# Sheet2.net
KiCad netlist of a schematic drawn in Altium Designer
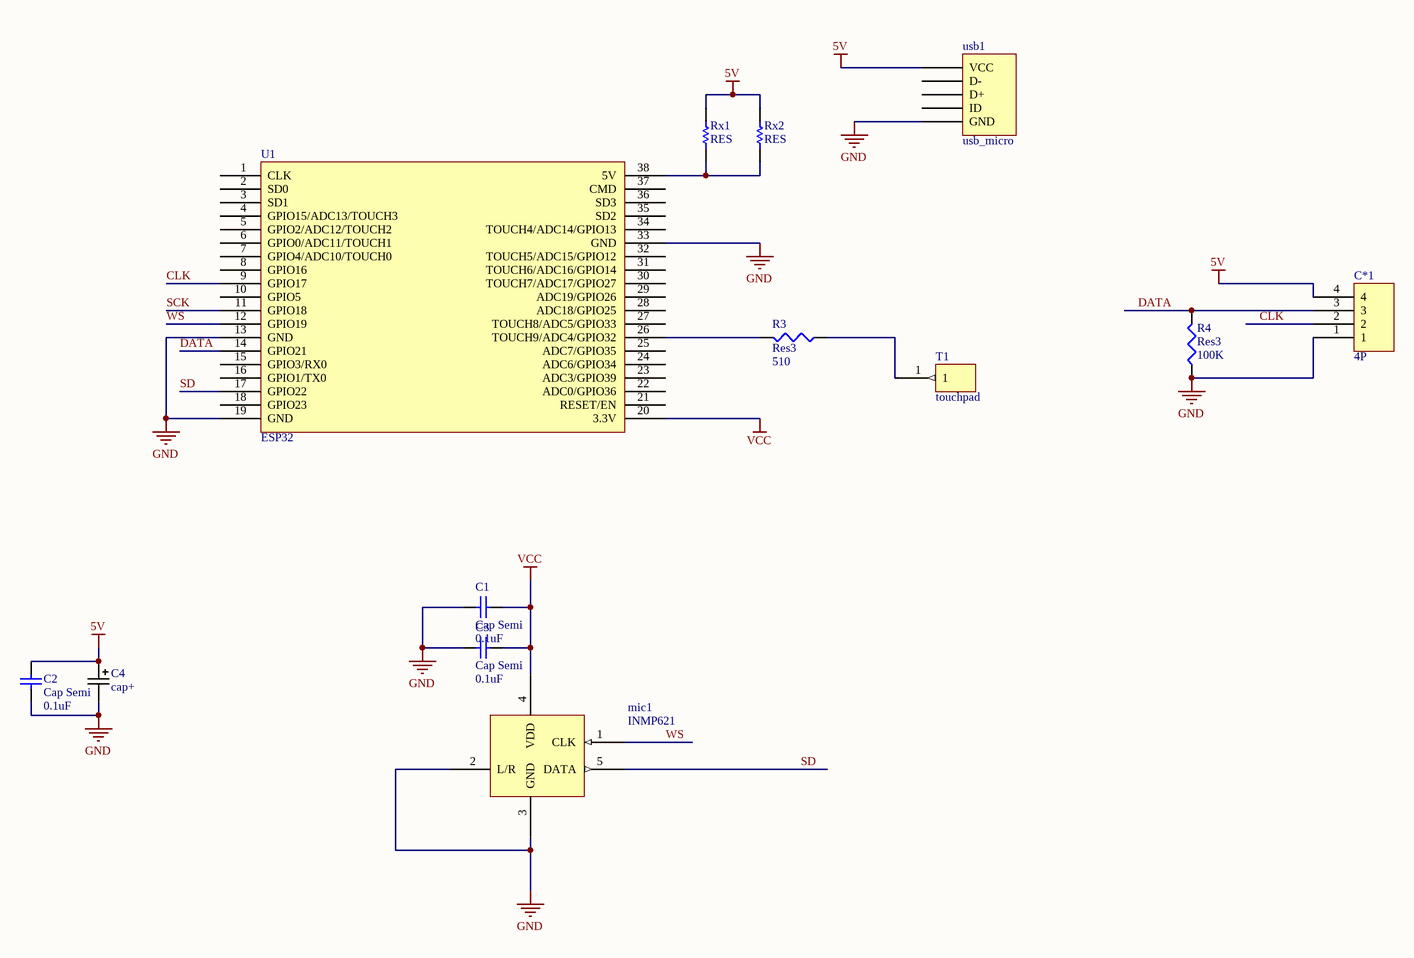
[diagram p0: Sheet2.SchDoc]

(export (version "E")
  (design (tool "Eeschema 10.0.6"))
  (components
    (comp (ref "C*1") (value "4P") (footprint "XH2.54_4P") (libsource (lib "connector") (part "4P")))
    (comp (ref "C1")
      (value "Cap Semi")
      (footprint "1608[0603]")
      (description "Capacitor (Semiconductor SIM Model)")
      (fields (field (name "ALTIUM_VALUE") "0.1uF") (field (name "PUBLISHER") "Altium Limited"))
      (libsource (lib "Miscellaneous Devices") (part "Cap Semi"))
    )
    (comp (ref "C2")
      (value "Cap Semi")
      (footprint "1608[0603]")
      (description "Capacitor (Semiconductor SIM Model)")
      (fields (field (name "ALTIUM_VALUE") "0.1uF") (field (name "PUBLISHER") "Altium Limited"))
      (libsource (lib "Miscellaneous Devices") (part "Cap Semi"))
    )
    (comp (ref "C3")
      (value "Cap Semi")
      (footprint "1608[0603]")
      (description "Capacitor (Semiconductor SIM Model)")
      (fields (field (name "ALTIUM_VALUE") "0.1uF") (field (name "PUBLISHER") "Altium Limited"))
      (libsource (lib "Miscellaneous Devices") (part "Cap Semi"))
    )
    (comp (ref "C4") (value "cap+") (footprint "cap_SMD") (libsource (lib "common") (part "cap+")))
    (comp (ref "mic1") (value "INMP621") (footprint "INMP621") (libsource (lib "ic") (part "INMP621")))
    (comp (ref "R3")
      (value "Res3")
      (footprint "6-0805_M")
      (description "Resistor")
      (fields (field (name "ALTIUM_VALUE") "510") (field (name "PUBLISHER") "Altium Limited"))
      (libsource (lib "Miscellaneous Devices") (part "Res3"))
    )
    (comp (ref "R4")
      (value "Res3")
      (footprint "6-0805_M")
      (description "Resistor")
      (fields (field (name "ALTIUM_VALUE") "100K") (field (name "PUBLISHER") "Altium Limited"))
      (libsource (lib "Miscellaneous Devices") (part "Res3"))
    )
    (comp (ref "Rx1") (value "RES") (footprint "RES_2512") (libsource (lib "common") (part "RES")))
    (comp (ref "Rx2") (value "RES") (footprint "RES_2512") (libsource (lib "common") (part "RES")))
    (comp (ref "T1") (value "touchpad") (footprint "touchpad") (libsource (lib "input") (part "touchpad")))
    (comp (ref "U1") (value "ESP32") (footprint "ESP32_S") (libsource (lib "ic") (part "ESP32")))
    (comp (ref "usb1")
      (value "usb_micro")
      (footprint "USB_micro")
      (libsource (lib "input") (part "usb_micro"))
    )
  )
  (nets
    (net (code "1") (name "/CLK") (class "Default")
      (node (ref "C*1") (pin "2") (pinfunction "2_2") (pintype "passive"))
      (node (ref "U1") (pin "9") (pinfunction "GPIO17_9") (pintype "passive"))
    )
    (net (code "2") (name "/DATA") (class "Default")
      (node (ref "C*1") (pin "3") (pinfunction "3_3") (pintype "passive"))
      (node (ref "R4") (pin "2") (pinfunction "2_2") (pintype "passive"))
      (node (ref "U1") (pin "14") (pinfunction "GPIO21_14") (pintype "passive"))
    )
    (net (code "3") (name "/SCK") (class "Default")
      (node (ref "U1") (pin "11") (pinfunction "GPIO18_11") (pintype "passive"))
    )
    (net (code "4") (name "/SD") (class "Default")
      (node (ref "U1") (pin "17") (pinfunction "GPIO22_17") (pintype "passive"))
      (node (ref "mic1") (pin "5") (pinfunction "DATA_5") (pintype "output"))
    )
    (net (code "5") (name "/WS") (class "Default")
      (node (ref "U1") (pin "12") (pinfunction "GPIO19_12") (pintype "passive"))
      (node (ref "mic1") (pin "1") (pinfunction "CLK_1") (pintype "input"))
    )
    (net (code "6") (name "5V") (class "Default")
      (node (ref "C*1") (pin "4") (pinfunction "4_4") (pintype "passive"))
      (node (ref "C2") (pin "2") (pinfunction "2_2") (pintype "passive"))
      (node (ref "C4") (pin "1") (pinfunction "1_1") (pintype "passive"))
      (node (ref "Rx1") (pin "2") (pinfunction "2_2") (pintype "passive"))
      (node (ref "Rx2") (pin "2") (pinfunction "2_2") (pintype "passive"))
      (node (ref "usb1") (pin "1") (pinfunction "VCC_1") (pintype "passive"))
    )
    (net (code "7") (name "GND") (class "Default")
      (node (ref "C*1") (pin "1") (pinfunction "1_1") (pintype "passive"))
      (node (ref "C1") (pin "2") (pinfunction "2_2") (pintype "passive"))
      (node (ref "C2") (pin "1") (pinfunction "1_1") (pintype "passive"))
      (node (ref "C3") (pin "2") (pinfunction "2_2") (pintype "passive"))
      (node (ref "C4") (pin "2") (pinfunction "2_2") (pintype "passive"))
      (node (ref "R4") (pin "1") (pinfunction "1_1") (pintype "passive"))
      (node (ref "U1") (pin "13") (pinfunction "GND_13") (pintype "passive"))
      (node (ref "U1") (pin "19") (pinfunction "GND_19") (pintype "passive"))
      (node (ref "U1") (pin "33") (pinfunction "GND_33") (pintype "passive"))
      (node (ref "mic1") (pin "2") (pinfunction "L/R_2") (pintype "passive"))
      (node (ref "mic1") (pin "3") (pinfunction "GND_3") (pintype "passive"))
      (node (ref "usb1") (pin "5") (pinfunction "GND_5") (pintype "passive"))
    )
    (net (code "8") (name "Net-(R3-Pad1)") (class "Default")
      (node (ref "R3") (pin "1") (pinfunction "1_1") (pintype "passive"))
      (node (ref "T1") (pin "1") (pinfunction "1_1") (pintype "output"))
    )
    (net (code "9") (name "Net-(U1-5V)") (class "Default")
      (node (ref "Rx1") (pin "1") (pinfunction "1_1") (pintype "passive"))
      (node (ref "Rx2") (pin "1") (pinfunction "1_1") (pintype "passive"))
      (node (ref "U1") (pin "38") (pinfunction "5V_38") (pintype "passive"))
    )
    (net (code "10") (name "Net-(U1-TOUCH9{slash}ADC4{slash}GPIO32)") (class "Default")
      (node (ref "R3") (pin "2") (pinfunction "2_2") (pintype "passive"))
      (node (ref "U1") (pin "26") (pinfunction "TOUCH9/ADC4/GPIO32_26") (pintype "passive"))
    )
    (net (code "11") (name "VCC") (class "Default")
      (node (ref "C1") (pin "1") (pinfunction "1_1") (pintype "passive"))
      (node (ref "C3") (pin "1") (pinfunction "1_1") (pintype "passive"))
      (node (ref "U1") (pin "20") (pinfunction "3.3V_20") (pintype "passive"))
      (node (ref "mic1") (pin "4") (pinfunction "VDD_4") (pintype "passive"))
    )
    (net (code "12") (name "unconnected-(U1-ADC0{slash}GPIO36-Pad22)") (class "Default")
      (node (ref "U1") (pin "22") (pinfunction "ADC0/GPIO36_22") (pintype "passive"))
    )
    (net (code "13") (name "unconnected-(U1-ADC3{slash}GPIO39-Pad23)") (class "Default")
      (node (ref "U1") (pin "23") (pinfunction "ADC3/GPIO39_23") (pintype "passive"))
    )
    (net (code "14") (name "unconnected-(U1-ADC6{slash}GPIO34-Pad24)") (class "Default")
      (node (ref "U1") (pin "24") (pinfunction "ADC6/GPIO34_24") (pintype "passive"))
    )
    (net (code "15") (name "unconnected-(U1-ADC7{slash}GPIO35-Pad25)") (class "Default")
      (node (ref "U1") (pin "25") (pinfunction "ADC7/GPIO35_25") (pintype "passive"))
    )
    (net (code "16") (name "unconnected-(U1-ADC18{slash}GPIO25-Pad28)") (class "Default")
      (node (ref "U1") (pin "28") (pinfunction "ADC18/GPIO25_28") (pintype "passive"))
    )
    (net (code "17") (name "unconnected-(U1-ADC19{slash}GPIO26-Pad29)") (class "Default")
      (node (ref "U1") (pin "29") (pinfunction "ADC19/GPIO26_29") (pintype "passive"))
    )
    (net (code "18") (name "unconnected-(U1-CLK-Pad1)") (class "Default")
      (node (ref "U1") (pin "1") (pinfunction "CLK_1") (pintype "passive"))
    )
    (net (code "19") (name "unconnected-(U1-CMD-Pad37)") (class "Default")
      (node (ref "U1") (pin "37") (pinfunction "CMD_37") (pintype "passive"))
    )
    (net (code "20") (name "unconnected-(U1-GPIO0{slash}ADC11{slash}TOUCH1-Pad6)") (class "Default")
      (node (ref "U1") (pin "6") (pinfunction "GPIO0/ADC11/TOUCH1_6") (pintype "passive"))
    )
    (net (code "21") (name "unconnected-(U1-GPIO1{slash}TX0-Pad16)") (class "Default")
      (node (ref "U1") (pin "16") (pinfunction "GPIO1/TX0_16") (pintype "passive"))
    )
    (net (code "22") (name "unconnected-(U1-GPIO2{slash}ADC12{slash}TOUCH2-Pad5)") (class "Default")
      (node (ref "U1") (pin "5") (pinfunction "GPIO2/ADC12/TOUCH2_5") (pintype "passive"))
    )
    (net (code "23") (name "unconnected-(U1-GPIO3{slash}RX0-Pad15)") (class "Default")
      (node (ref "U1") (pin "15") (pinfunction "GPIO3/RX0_15") (pintype "passive"))
    )
    (net (code "24") (name "unconnected-(U1-GPIO4{slash}ADC10{slash}TOUCH0-Pad7)") (class "Default")
      (node (ref "U1") (pin "7") (pinfunction "GPIO4/ADC10/TOUCH0_7") (pintype "passive"))
    )
    (net (code "25") (name "unconnected-(U1-GPIO5-Pad10)") (class "Default")
      (node (ref "U1") (pin "10") (pinfunction "GPIO5_10") (pintype "passive"))
    )
    (net (code "26") (name "unconnected-(U1-GPIO15{slash}ADC13{slash}TOUCH3-Pad4)") (class "Default")
      (node (ref "U1") (pin "4") (pinfunction "GPIO15/ADC13/TOUCH3_4") (pintype "passive"))
    )
    (net (code "27") (name "unconnected-(U1-GPIO16-Pad8)") (class "Default")
      (node (ref "U1") (pin "8") (pinfunction "GPIO16_8") (pintype "passive"))
    )
    (net (code "28") (name "unconnected-(U1-GPIO23-Pad18)") (class "Default")
      (node (ref "U1") (pin "18") (pinfunction "GPIO23_18") (pintype "passive"))
    )
    (net (code "29") (name "unconnected-(U1-RESET{slash}EN-Pad21)") (class "Default")
      (node (ref "U1") (pin "21") (pinfunction "RESET/EN_21") (pintype "passive"))
    )
    (net (code "30") (name "unconnected-(U1-SD0-Pad2)") (class "Default")
      (node (ref "U1") (pin "2") (pinfunction "SD0_2") (pintype "passive"))
    )
    (net (code "31") (name "unconnected-(U1-SD1-Pad3)") (class "Default")
      (node (ref "U1") (pin "3") (pinfunction "SD1_3") (pintype "passive"))
    )
    (net (code "32") (name "unconnected-(U1-SD2-Pad35)") (class "Default")
      (node (ref "U1") (pin "35") (pinfunction "SD2_35") (pintype "passive"))
    )
    (net (code "33") (name "unconnected-(U1-SD3-Pad36)") (class "Default")
      (node (ref "U1") (pin "36") (pinfunction "SD3_36") (pintype "passive"))
    )
    (net (code "34") (name "unconnected-(U1-TOUCH4{slash}ADC14{slash}GPIO13-Pad34)") (class "Default")
      (node (ref "U1") (pin "34") (pinfunction "TOUCH4/ADC14/GPIO13_34") (pintype "passive"))
    )
    (net (code "35") (name "unconnected-(U1-TOUCH5{slash}ADC15{slash}GPIO12-Pad32)") (class "Default")
      (node (ref "U1") (pin "32") (pinfunction "TOUCH5/ADC15/GPIO12_32") (pintype "passive"))
    )
    (net (code "36") (name "unconnected-(U1-TOUCH6{slash}ADC16{slash}GPIO14-Pad31)") (class "Default")
      (node (ref "U1") (pin "31") (pinfunction "TOUCH6/ADC16/GPIO14_31") (pintype "passive"))
    )
    (net (code "37") (name "unconnected-(U1-TOUCH7{slash}ADC17{slash}GPIO27-Pad30)") (class "Default")
      (node (ref "U1") (pin "30") (pinfunction "TOUCH7/ADC17/GPIO27_30") (pintype "passive"))
    )
    (net (code "38") (name "unconnected-(U1-TOUCH8{slash}ADC5{slash}GPIO33-Pad27)") (class "Default")
      (node (ref "U1") (pin "27") (pinfunction "TOUCH8/ADC5/GPIO33_27") (pintype "passive"))
    )
    (net (code "39") (name "unconnected-(usb1-D+-Pad3)") (class "Default")
      (node (ref "usb1") (pin "3") (pinfunction "D+_3") (pintype "passive"))
    )
    (net (code "40") (name "unconnected-(usb1-D--Pad2)") (class "Default")
      (node (ref "usb1") (pin "2") (pinfunction "D-_2") (pintype "passive"))
    )
    (net (code "41") (name "unconnected-(usb1-ID-Pad4)") (class "Default")
      (node (ref "usb1") (pin "4") (pinfunction "ID_4") (pintype "passive"))
    )
  )
)
